# Rev_C_Power.net
KiCad netlist of a schematic drawn in Altium Designer
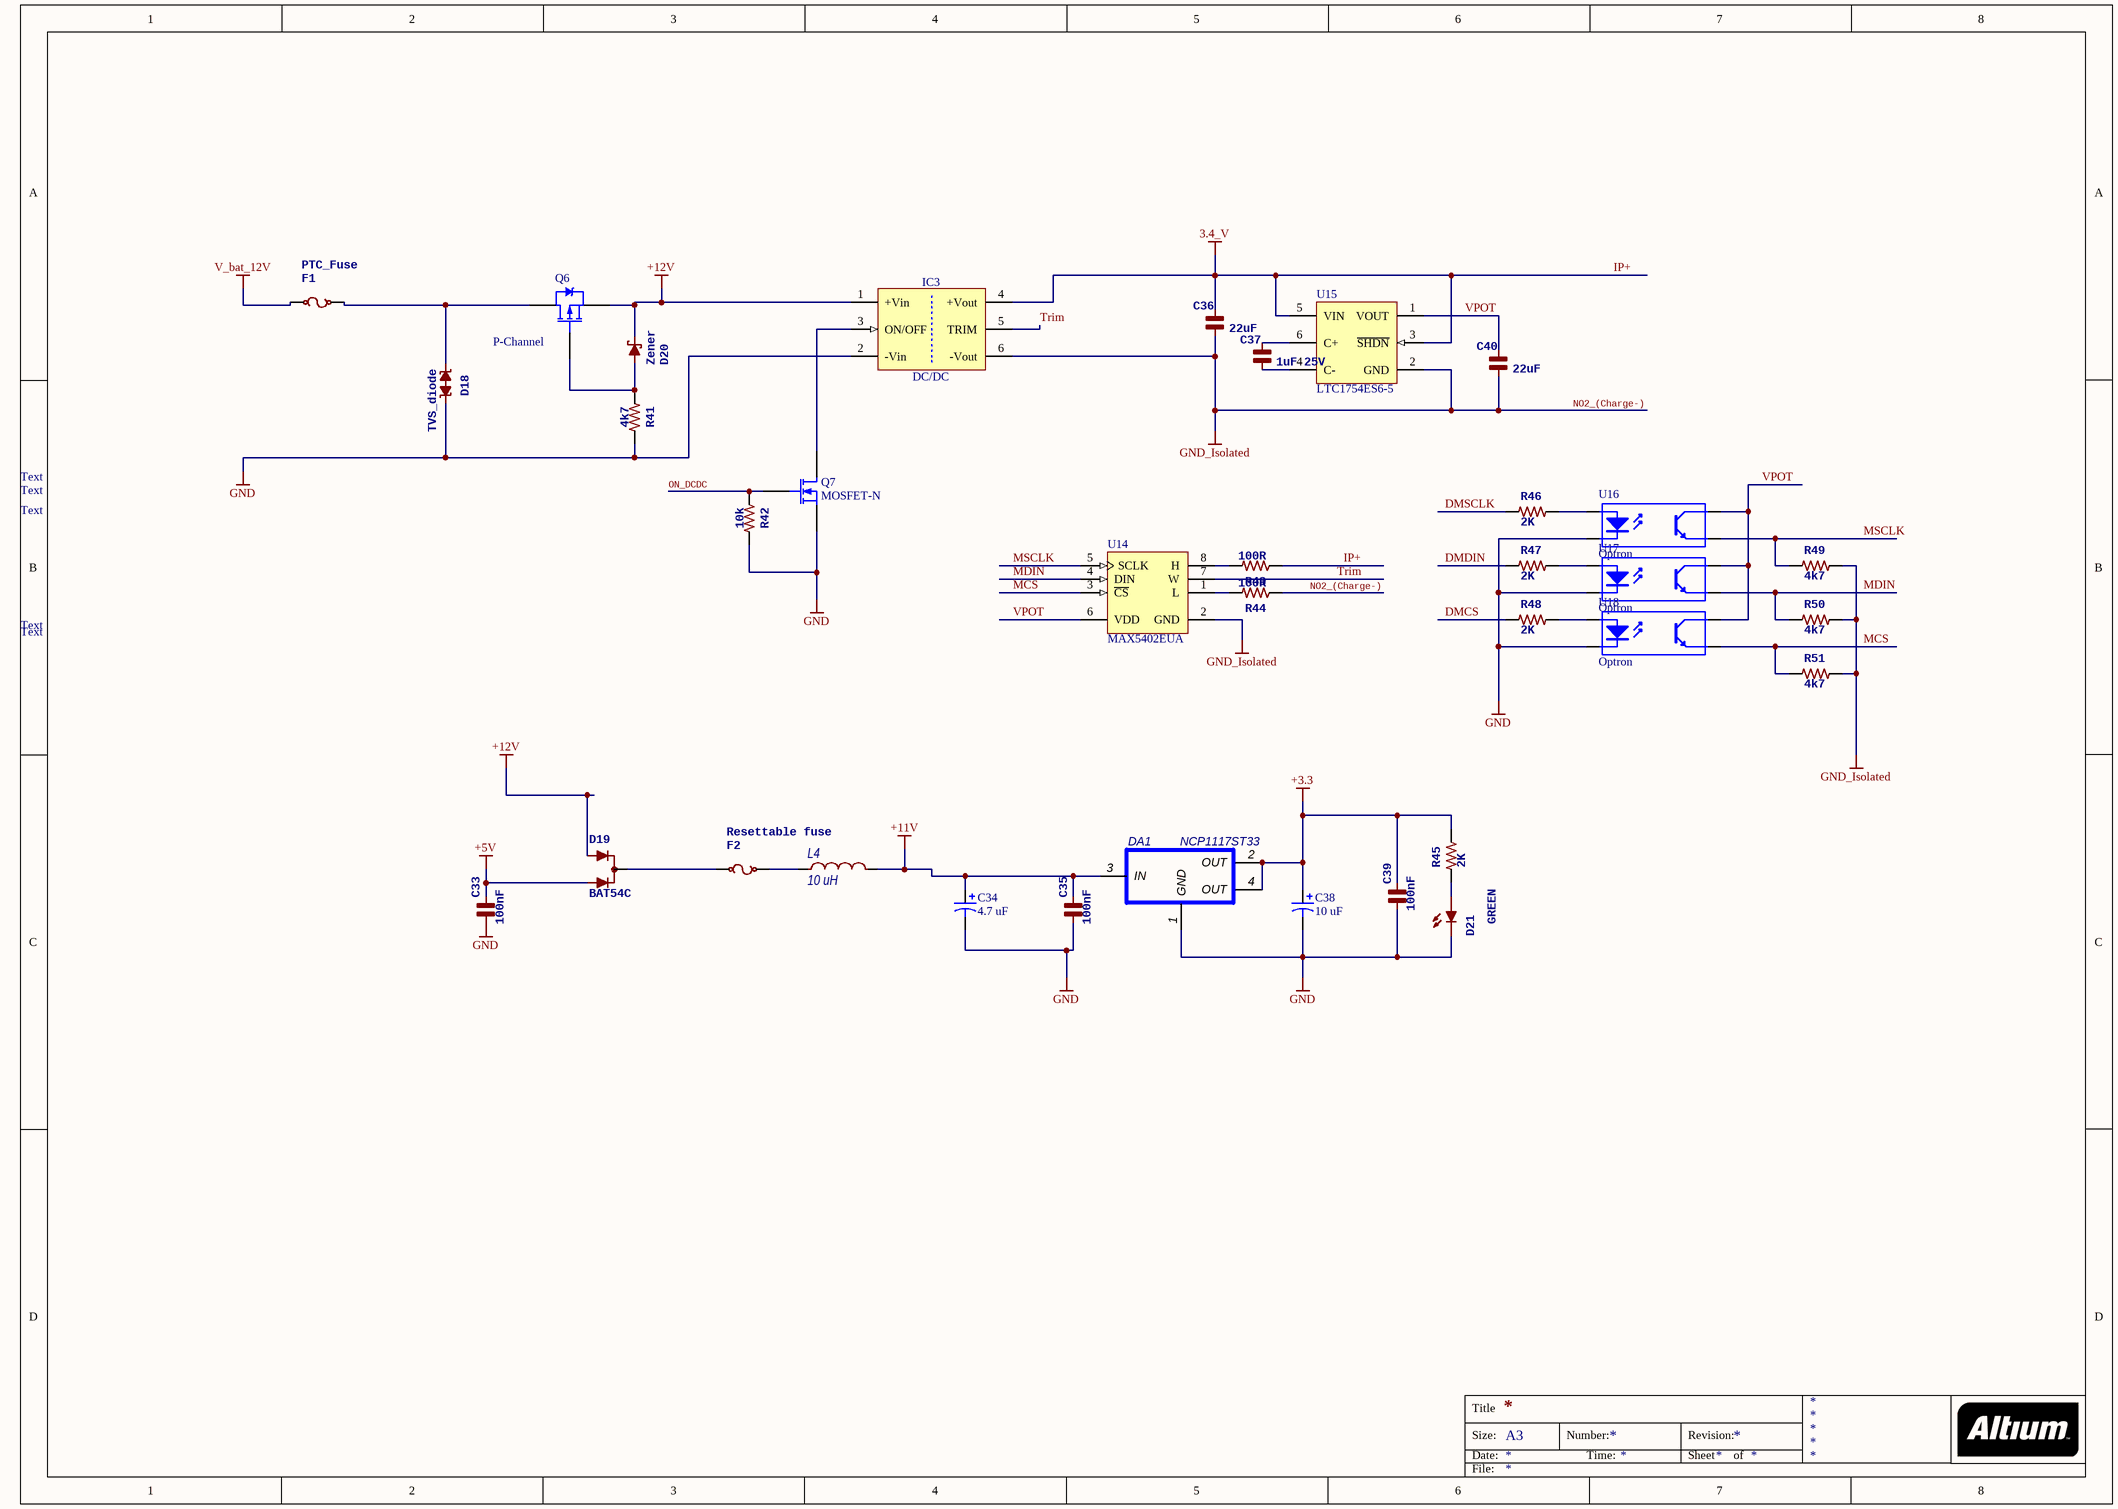
[diagram p0: Rev_C_Power.SchDoc]

(export (version "E")
  (design (tool "Eeschema 10.0.6"))
  (components
    (comp (ref "C33")
      (value "100nF")
      (footprint "C0603")
      (description "GRM188R71E104KA01J")
      (fields (field (name "MF") "MURATA") (field (name "MPN") "GRM188F51E104ZA01D"))
      (libsource (lib "balan_1") (part "C_0603"))
    )
    (comp (ref "C34")
      (value "4.7 uF")
      (footprint "SMD D")
      (description "293D475X9050D2WE3")
      (fields (field (name "PUBLISHER") "Altium Limited"))
      (libsource (lib "ev-board_1") (part "Cap Pol2"))
    )
    (comp (ref "C35")
      (value "100nF")
      (footprint "C0603")
      (description "GRM188R71E104KA01J")
      (fields (field (name "MF") "MURATA") (field (name "MPN") "GRM188F51E104ZA01D"))
      (libsource (lib "balan_1") (part "C_0603"))
    )
    (comp (ref "C36")
      (value "22uF")
      (footprint "C0603")
      (description "ZRB18AR61A226ME01L")
      (fields (field (name "MF") "MURATA"))
      (libsource (lib "balan_1") (part "C_0603"))
    )
    (comp (ref "C37")
      (value "1uF 25V")
      (footprint "C0603")
      (description "885012106022")
      (fields (field (name "MF") "MURATA"))
      (libsource (lib "balan_1") (part "C_0603"))
    )
    (comp (ref "C38")
      (value "10 uF")
      (footprint "SMD A")
      (description "THJA106K010AJN")
      (fields (field (name "PUBLISHER") "Altium Limited"))
      (libsource (lib "ev-board_1") (part "Cap Pol2"))
    )
    (comp (ref "C39")
      (value "100nF")
      (footprint "C0603")
      (description "GRM188R71E104KA01J")
      (fields (field (name "MF") "MURATA") (field (name "MPN") "GRM188F51E104ZA01D"))
      (libsource (lib "balan_1") (part "C_0603"))
    )
    (comp (ref "C40")
      (value "22uF")
      (footprint "C0603")
      (description "ZRB18AR61A226ME01L")
      (fields (field (name "MF") "MURATA"))
      (libsource (lib "balan_1") (part "C_0603"))
    )
    (comp (ref "D18")
      (value "TVS_diode")
      (footprint "SMB_BIDIR")
      (description "SMAJ17CA")
      (libsource (lib "ev-board_1") (part "DIODE-TVS-SMAJ_1"))
    )
    (comp (ref "D19")
      (value "BAT54C")
      (footprint "SOT23")
      (description "BAT54C-G")
      (libsource (lib "ev-board_1") (part "BAT54C"))
    )
    (comp (ref "D20")
      (value "Zener")
      (footprint "SOD523")
      (description "BZT52C10T-7")
      (libsource (lib "ev-board_1") (part "SCHOTTKY-DIODESMA_2"))
    )
    (comp (ref "D21")
      (value "GREEN")
      (footprint "CHIP-LED0603")
      (description "150060VS75000")
      (fields (field (name "MANUFACTURER PART NUMBER") "150060RS75000"))
      (libsource (lib "ev-board_1") (part "LEDCHIP-LED0603_2"))
    )
    (comp (ref "DA1")
      (value "NCP1117ST33")
      (footprint "SOT223")
      (description "NCP1117LPST33T3G")
      (libsource (lib "X_Bee") (part "NCP1117ST33"))
    )
    (comp (ref "F1")
      (value "PTC_Fuse")
      (footprint "RUEF250")
      (description "RUEF250")
      (libsource (lib "ev-board_1") (part "RUEF250"))
    )
    (comp (ref "F2")
      (value "Resettable fuse")
      (footprint "R1206")
      (description "0ZCJ0050AF2E")
      (libsource (lib "ev-board_1") (part "3216CP-3A_1"))
    )
    (comp (ref "IC3")
      (value "DC/DC")
      (footprint "DCDC_1x1")
      (description "PDQ30-Q24-S3-D")
      (libsource (lib "ev-board_1") (part "DCDC_TDK_30_Single Output"))
    )
    (comp (ref "L4")
      (value "10 uH")
      (footprint "C0603")
      (description "KLZ1608MHR100WTD25")
      (libsource (lib "Passive") (part "L2"))
    )
    (comp (ref "Q6")
      (value "P-Channel")
      (footprint "SO-8 - IRF FET")
      (description "FDS6681Z")
      (fields (field (name "PUBLISHER") "Altium Limited"))
      (libsource (lib "ev-board_1") (part "PMOS-2"))
    )
    (comp (ref "Q7")
      (value "MOSFET-N")
      (footprint "SOT23-3N")
      (description "NTR4170NT1G")
      (fields (field (name "PUBLISHER") "Altium Limited"))
      (libsource (lib "balan_1") (part "MOSFET-N"))
    )
    (comp (ref "R41")
      (value "4k7")
      (footprint "R0603")
      (description "RC0603FR-074K7L")
      (libsource (lib "ev-board_1") (part "R_0603_18"))
    )
    (comp (ref "R42")
      (value "10k")
      (footprint "R0603")
      (description "RC0603FR-0710KL")
      (libsource (lib "ev-board_1") (part "R_0603_18"))
    )
    (comp (ref "R43")
      (value "100R")
      (footprint "R0603")
      (description "RC0603FR-07100RL")
      (libsource (lib "") (part "R_0603_18_2"))
    )
    (comp (ref "R44")
      (value "100R")
      (footprint "R0603")
      (description "RC0603FR-07100RL")
      (libsource (lib "") (part "R_0603_18_2"))
    )
    (comp (ref "R45")
      (value "2K")
      (footprint "R0603")
      (description "RC0603FR-072KL")
      (libsource (lib "") (part "R_0603_18_3"))
    )
    (comp (ref "R46")
      (value "2K")
      (footprint "R0603")
      (description "RC0603FR-072KL")
      (libsource (lib "") (part "R_0603_18_1"))
    )
    (comp (ref "R47")
      (value "2K")
      (footprint "R0603")
      (description "RC0603FR-072KL")
      (libsource (lib "") (part "R_0603_18_1"))
    )
    (comp (ref "R48")
      (value "2K")
      (footprint "R0603")
      (description "RC0603FR-072KL")
      (libsource (lib "") (part "R_0603_18_1"))
    )
    (comp (ref "R49")
      (value "4k7")
      (footprint "R0603")
      (description "RC0603FR-074K7L")
      (libsource (lib "") (part "R_0603_18_1"))
    )
    (comp (ref "R50")
      (value "4k7")
      (footprint "R0603")
      (description "RC0603FR-074K7L")
      (libsource (lib "") (part "R_0603_18_1"))
    )
    (comp (ref "R51")
      (value "4k7")
      (footprint "R0603")
      (description "RC0603FR-074K7L")
      (libsource (lib "") (part "R_0603_18_1"))
    )
    (comp (ref "U14")
      (value "MAX5402EUA")
      (footprint "MAXM-U8-1_N")
      (description "MAX5402EUA+")
      (libsource (lib "ev-board_1") (part "MAX5402EUA"))
    )
    (comp (ref "U15")
      (value "LTC1754ES6-5")
      (footprint "LT-S6-6-SOT-23_N")
      (fields (field (name "MANUFACTURER") "Linear Technology"))
      (libsource (lib "ev-board_1") (part "LTC1754ES6-5"))
    )
    (comp (ref "U16")
      (value "Optron")
      (footprint "LTV-816S")
      (description "LTV-816S")
      (fields (field (name "PUBLISHER") "Altium Limited"))
      (libsource (lib "ev-board_1") (part "Optoisolator1"))
    )
    (comp (ref "U17")
      (value "Optron")
      (footprint "LTV-816S")
      (description "LTV-816S")
      (fields (field (name "PUBLISHER") "Altium Limited"))
      (libsource (lib "ev-board_1") (part "Optoisolator1"))
    )
    (comp (ref "U18")
      (value "Optron")
      (footprint "LTV-816S")
      (description "LTV-816S")
      (fields (field (name "PUBLISHER") "Altium Limited"))
      (libsource (lib "ev-board_1") (part "Optoisolator1"))
    )
  )
  (nets
    (net (code "1") (name "+3.3") (class "Default")
      (node (ref "C38") (pin "1") (pinfunction "1_1") (pintype "passive"))
      (node (ref "C39") (pin "2") (pinfunction "2_2") (pintype "passive"))
      (node (ref "DA1") (pin "2") (pinfunction "OUT_2") (pintype "passive"))
      (node (ref "DA1") (pin "4") (pinfunction "OUT_4") (pintype "passive"))
      (node (ref "R45") (pin "2") (pinfunction "2_2") (pintype "passive"))
    )
    (net (code "2") (name "+5V") (class "Default")
      (node (ref "C33") (pin "2") (pinfunction "2_2") (pintype "passive"))
      (node (ref "D19") (pin "2") (pinfunction "A2_2") (pintype "passive"))
    )
    (net (code "3") (name "+11V") (class "Default")
      (node (ref "C34") (pin "1") (pinfunction "1_1") (pintype "passive"))
      (node (ref "C35") (pin "2") (pinfunction "2_2") (pintype "passive"))
      (node (ref "DA1") (pin "3") (pinfunction "IN_3") (pintype "passive"))
      (node (ref "L4") (pin "2") (pinfunction "2_2") (pintype "passive"))
    )
    (net (code "4") (name "+12V") (class "Default")
      (node (ref "D19") (pin "1") (pinfunction "A1_1") (pintype "passive"))
      (node (ref "D20") (pin "C") (pinfunction "1_C") (pintype "passive"))
      (node (ref "IC3") (pin "1") (pinfunction "+Vin_1") (pintype "power_in"))
      (node (ref "Q6") (pin "1") (pinfunction "S_1") (pintype "passive"))
    )
    (net (code "5") (name "/DMCS") (class "Default")
      (node (ref "R48") (pin "1") (pinfunction "1_1") (pintype "passive"))
    )
    (net (code "6") (name "/DMDIN") (class "Default")
      (node (ref "R47") (pin "1") (pinfunction "1_1") (pintype "passive"))
    )
    (net (code "7") (name "/DMSCLK") (class "Default")
      (node (ref "R46") (pin "1") (pinfunction "1_1") (pintype "passive"))
    )
    (net (code "8") (name "/MCS") (class "Default")
      (node (ref "R51") (pin "1") (pinfunction "1_1") (pintype "passive"))
      (node (ref "U14") (pin "3") (pinfunction "~{CS}_3") (pintype "input"))
      (node (ref "U18") (pin "3") (pinfunction "E_3") (pintype "passive"))
    )
    (net (code "9") (name "/MDIN") (class "Default")
      (node (ref "R50") (pin "1") (pinfunction "1_1") (pintype "passive"))
      (node (ref "U14") (pin "4") (pinfunction "DIN_4") (pintype "input"))
      (node (ref "U17") (pin "3") (pinfunction "E_3") (pintype "passive"))
    )
    (net (code "10") (name "/MSCLK") (class "Default")
      (node (ref "R49") (pin "1") (pinfunction "1_1") (pintype "passive"))
      (node (ref "U14") (pin "5") (pinfunction "SCLK_5") (pintype "input"))
      (node (ref "U16") (pin "3") (pinfunction "E_3") (pintype "passive"))
    )
    (net (code "11") (name "/ON_DCDC") (class "Default")
      (node (ref "Q7") (pin "1") (pinfunction "G_1") (pintype "passive"))
      (node (ref "R42") (pin "1") (pinfunction "1_1") (pintype "passive"))
    )
    (net (code "12") (name "/Trim") (class "Default")
      (node (ref "IC3") (pin "5") (pinfunction "TRIM_5") (pintype "power_in"))
      (node (ref "U14") (pin "7") (pinfunction "W_7") (pintype "passive"))
    )
    (net (code "13") (name "/VPOT") (class "Default")
      (node (ref "C40") (pin "2") (pinfunction "2_2") (pintype "passive"))
      (node (ref "U14") (pin "6") (pinfunction "VDD_6") (pintype "power_in"))
      (node (ref "U15") (pin "1") (pinfunction "VOUT_1") (pintype "power_in"))
      (node (ref "U16") (pin "4") (pinfunction "C_4") (pintype "passive"))
      (node (ref "U17") (pin "4") (pinfunction "C_4") (pintype "passive"))
      (node (ref "U18") (pin "4") (pinfunction "C_4") (pintype "passive"))
    )
    (net (code "14") (name "3.4_V") (class "Default")
      (node (ref "C36") (pin "2") (pinfunction "2_2") (pintype "passive"))
      (node (ref "IC3") (pin "4") (pinfunction "+Vout_4") (pintype "power_in"))
      (node (ref "R43") (pin "1") (pinfunction "1_1") (pintype "passive"))
      (node (ref "U15") (pin "3") (pinfunction "~{SHDN}_3") (pintype "input"))
      (node (ref "U15") (pin "5") (pinfunction "VIN_5") (pintype "power_in"))
    )
    (net (code "15") (name "GND") (class "Default")
      (node (ref "C33") (pin "1") (pinfunction "1_1") (pintype "passive"))
      (node (ref "C34") (pin "2") (pinfunction "2_2") (pintype "passive"))
      (node (ref "C35") (pin "1") (pinfunction "1_1") (pintype "passive"))
      (node (ref "C38") (pin "2") (pinfunction "2_2") (pintype "passive"))
      (node (ref "C39") (pin "1") (pinfunction "1_1") (pintype "passive"))
      (node (ref "D18") (pin "2") (pinfunction "2_2") (pintype "passive"))
      (node (ref "D21") (pin "C") (pinfunction "C_C") (pintype "passive"))
      (node (ref "DA1") (pin "1") (pinfunction "GND_1") (pintype "passive"))
      (node (ref "IC3") (pin "2") (pinfunction "-Vin_2") (pintype "power_in"))
      (node (ref "Q7") (pin "2") (pinfunction "S_2") (pintype "passive"))
      (node (ref "R41") (pin "2") (pinfunction "2_2") (pintype "passive"))
      (node (ref "R42") (pin "2") (pinfunction "2_2") (pintype "passive"))
      (node (ref "U16") (pin "2") (pinfunction "K_2") (pintype "passive"))
      (node (ref "U17") (pin "2") (pinfunction "K_2") (pintype "passive"))
      (node (ref "U18") (pin "2") (pinfunction "K_2") (pintype "passive"))
    )
    (net (code "16") (name "GND_Isolated") (class "Default")
      (node (ref "C36") (pin "1") (pinfunction "1_1") (pintype "passive"))
      (node (ref "C40") (pin "1") (pinfunction "1_1") (pintype "passive"))
      (node (ref "IC3") (pin "6") (pinfunction "-Vout_6") (pintype "power_in"))
      (node (ref "R44") (pin "1") (pinfunction "1_1") (pintype "passive"))
      (node (ref "R49") (pin "2") (pinfunction "2_2") (pintype "passive"))
      (node (ref "R50") (pin "2") (pinfunction "2_2") (pintype "passive"))
      (node (ref "R51") (pin "2") (pinfunction "2_2") (pintype "passive"))
      (node (ref "U14") (pin "2") (pinfunction "GND_2") (pintype "power_in"))
      (node (ref "U15") (pin "2") (pinfunction "GND_2") (pintype "power_in"))
    )
    (net (code "17") (name "Net-(D19-C)") (class "Default")
      (node (ref "D19") (pin "3") (pinfunction "C_3") (pintype "passive"))
      (node (ref "F2") (pin "1") (pinfunction "1_1") (pintype "passive"))
    )
    (net (code "18") (name "Net-(D20-2)") (class "Default")
      (node (ref "D20") (pin "A") (pinfunction "2_A") (pintype "passive"))
      (node (ref "Q6") (pin "2") (pinfunction "G_2") (pintype "passive"))
      (node (ref "R41") (pin "1") (pinfunction "1_1") (pintype "passive"))
    )
    (net (code "19") (name "Net-(D21-PadA)") (class "Default")
      (node (ref "D21") (pin "A") (pinfunction "A_A") (pintype "passive"))
      (node (ref "R45") (pin "1") (pinfunction "1_1") (pintype "passive"))
    )
    (net (code "20") (name "Net-(F2-Pad2)") (class "Default")
      (node (ref "F2") (pin "2") (pinfunction "2_2") (pintype "passive"))
      (node (ref "L4") (pin "1") (pinfunction "1_1") (pintype "passive"))
    )
    (net (code "21") (name "Net-(IC3-ON{slash}OFF)") (class "Default")
      (node (ref "IC3") (pin "3") (pinfunction "ON/OFF_3") (pintype "input"))
      (node (ref "Q7") (pin "3") (pinfunction "D_3") (pintype "passive"))
    )
    (net (code "22") (name "Net-(Q6-D)") (class "Default")
      (node (ref "D18") (pin "1") (pinfunction "1_1") (pintype "passive"))
      (node (ref "F1") (pin "2") (pinfunction "2_2") (pintype "passive"))
      (node (ref "Q6") (pin "3") (pinfunction "D_3") (pintype "passive"))
    )
    (net (code "23") (name "Net-(U14-H)") (class "Default")
      (node (ref "R43") (pin "2") (pinfunction "2_2") (pintype "passive"))
      (node (ref "U14") (pin "8") (pinfunction "H_8") (pintype "passive"))
    )
    (net (code "24") (name "Net-(U14-L)") (class "Default")
      (node (ref "R44") (pin "2") (pinfunction "2_2") (pintype "passive"))
      (node (ref "U14") (pin "1") (pinfunction "L_1") (pintype "passive"))
    )
    (net (code "25") (name "Net-(U15-C+)") (class "Default")
      (node (ref "C37") (pin "2") (pinfunction "2_2") (pintype "passive"))
      (node (ref "U15") (pin "6") (pinfunction "C+_6") (pintype "passive"))
    )
    (net (code "26") (name "Net-(U15-C-)") (class "Default")
      (node (ref "C37") (pin "1") (pinfunction "1_1") (pintype "passive"))
      (node (ref "U15") (pin "4") (pinfunction "C-_4") (pintype "passive"))
    )
    (net (code "27") (name "Net-(U16-A)") (class "Default")
      (node (ref "R46") (pin "2") (pinfunction "2_2") (pintype "passive"))
      (node (ref "U16") (pin "1") (pinfunction "A_1") (pintype "passive"))
    )
    (net (code "28") (name "Net-(U17-A)") (class "Default")
      (node (ref "R47") (pin "2") (pinfunction "2_2") (pintype "passive"))
      (node (ref "U17") (pin "1") (pinfunction "A_1") (pintype "passive"))
    )
    (net (code "29") (name "Net-(U18-A)") (class "Default")
      (node (ref "R48") (pin "2") (pinfunction "2_2") (pintype "passive"))
      (node (ref "U18") (pin "1") (pinfunction "A_1") (pintype "passive"))
    )
    (net (code "30") (name "V_bat_12V") (class "Default")
      (node (ref "F1") (pin "1") (pinfunction "1_1") (pintype "passive"))
    )
  )
)
